# motor.net
KiCad netlist of a schematic drawn in Altium Designer
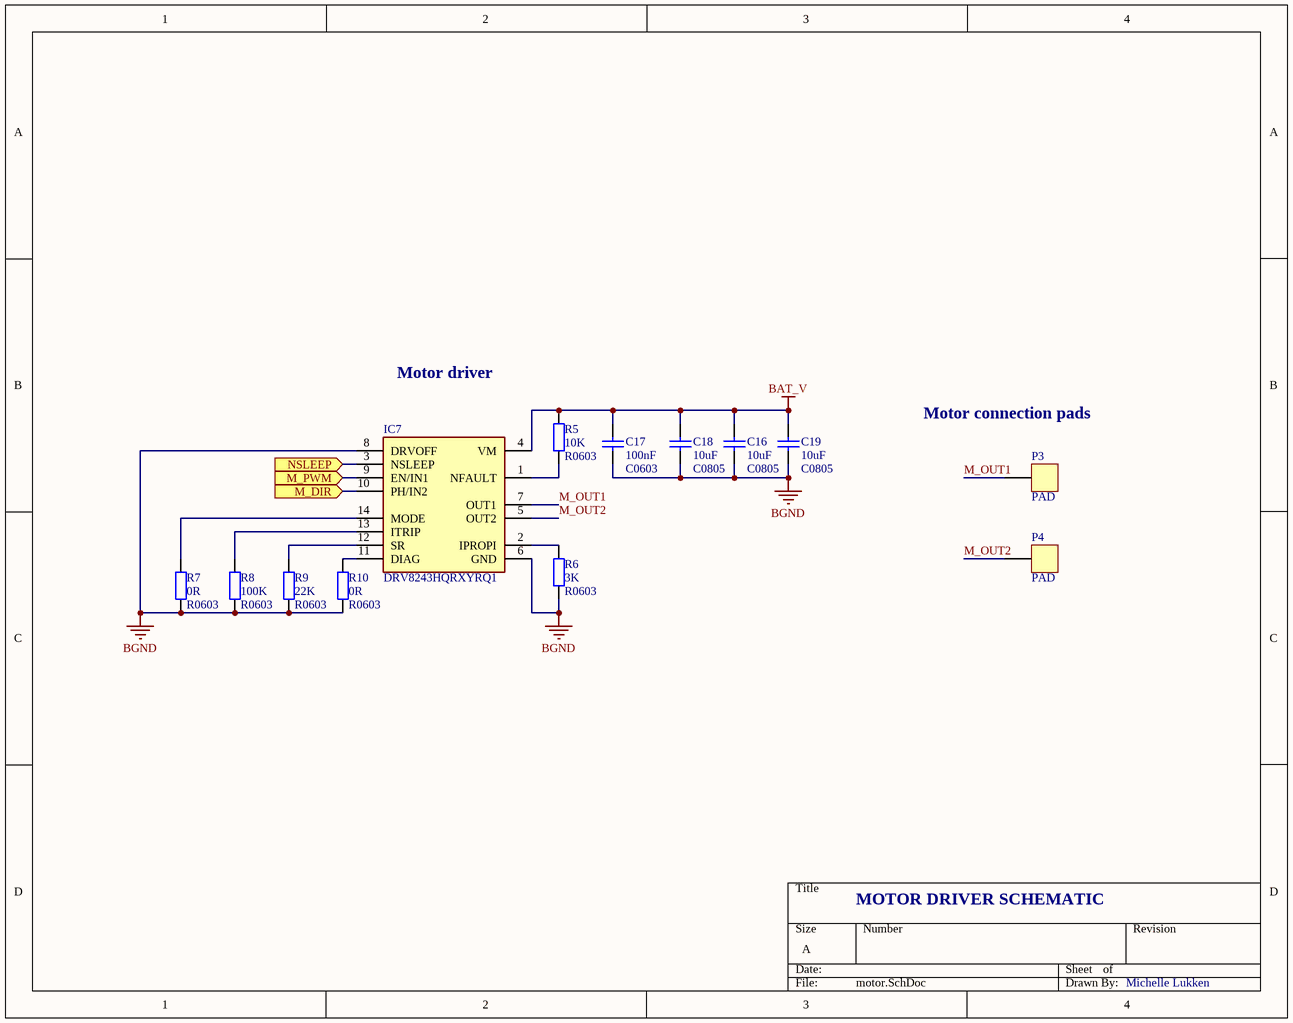
[diagram p0: motor.SchDoc]

(export (version "E")
  (design (tool "Eeschema 10.0.6"))
  (components
    (comp (ref "C16")
      (value "10uF*V")
      (footprint "C0805")
      (description "Ceramic capacitor")
      (fields (field (name "CAPACITANCE") "10uF"))
      (libsource (lib "Component Library INTLIB") (part "Capacitor"))
    )
    (comp (ref "C17")
      (value "100nF*V")
      (footprint "PCB Passives:C0603")
      (description "Ceramic capacitor")
      (fields (field (name "CAPACITANCE") "100nF"))
      (libsource (lib "DeltaX_basketball_mikro") (part "Capacitor"))
    )
    (comp (ref "C18")
      (value "10uF*V")
      (footprint "C0805")
      (description "Ceramic capacitor")
      (fields (field (name "CAPACITANCE") "10uF"))
      (libsource (lib "Component Library INTLIB") (part "Capacitor"))
    )
    (comp (ref "C19")
      (value "10uF*V")
      (footprint "C0805")
      (description "Ceramic capacitor")
      (fields (field (name "CAPACITANCE") "10uF"))
      (libsource (lib "Component Library INTLIB") (part "Capacitor"))
    )
    (comp (ref "IC7")
      (value "DRV8243HQRXYRQ1")
      (footprint "SamacSys:DRV8243HQRXYRQ1")
      (description "Integrated Circuit")
      (libsource (lib "DeltaX_basketball_mikro") (part "DRV8243HQRXYRQ1"))
    )
    (comp (ref "P3")
      (value "PAD")
      (footprint "SamacSys:PAD")
      (libsource (lib "DeltaX_basketball_mikro") (part "PAD"))
    )
    (comp (ref "P4")
      (value "PAD")
      (footprint "SamacSys:PAD")
      (libsource (lib "DeltaX_basketball_mikro") (part "PAD"))
    )
    (comp (ref "R5")
      (value "10K")
      (footprint "R0603")
      (description "Resistor")
      (fields (field (name "RESISTANCE") "10K"))
      (libsource (lib "Component Library INTLIB") (part "Resistor"))
    )
    (comp (ref "R6")
      (value "3K")
      (footprint "R0603")
      (description "Resistor")
      (fields (field (name "RESISTANCE") "3K"))
      (libsource (lib "Component Library INTLIB") (part "Resistor"))
    )
    (comp (ref "R7")
      (value "0R")
      (footprint "R0603")
      (description "Resistor")
      (fields (field (name "RESISTANCE") "0R"))
      (libsource (lib "Component Library INTLIB") (part "Resistor"))
    )
    (comp (ref "R8")
      (value "100K")
      (footprint "R0603")
      (description "Resistor")
      (fields (field (name "RESISTANCE") "100K"))
      (libsource (lib "Component Library INTLIB") (part "Resistor"))
    )
    (comp (ref "R9")
      (value "22K")
      (footprint "R0603")
      (description "Resistor")
      (fields (field (name "RESISTANCE") "22K"))
      (libsource (lib "Component Library INTLIB") (part "Resistor"))
    )
    (comp (ref "R10")
      (value "0R")
      (footprint "R0603")
      (description "Resistor")
      (fields (field (name "RESISTANCE") "0R"))
      (libsource (lib "Component Library INTLIB") (part "Resistor"))
    )
  )
  (nets
    (net (code "1") (name "/M_DIR") (class "Default")
      (node (ref "IC7") (pin "10") (pinfunction "PH/IN2_10") (pintype "passive"))
    )
    (net (code "2") (name "/M_OUT1") (class "Default")
      (node (ref "IC7") (pin "7") (pinfunction "OUT1_7") (pintype "passive"))
      (node (ref "P3") (pin "1") (pinfunction "PAD_1") (pintype "passive"))
    )
    (net (code "3") (name "/M_OUT2") (class "Default")
      (node (ref "IC7") (pin "5") (pinfunction "OUT2_5") (pintype "passive"))
      (node (ref "P4") (pin "1") (pinfunction "PAD_1") (pintype "passive"))
    )
    (net (code "4") (name "/M_PWM") (class "Default")
      (node (ref "IC7") (pin "9") (pinfunction "EN/IN1_9") (pintype "passive"))
    )
    (net (code "5") (name "/NSLEEP") (class "Default")
      (node (ref "IC7") (pin "3") (pinfunction "NSLEEP_3") (pintype "passive"))
    )
    (net (code "6") (name "BAT_V") (class "Default")
      (node (ref "C16") (pin "2") (pinfunction "2_2") (pintype "passive"))
      (node (ref "C17") (pin "2") (pinfunction "2_2") (pintype "passive"))
      (node (ref "C18") (pin "2") (pinfunction "2_2") (pintype "passive"))
      (node (ref "C19") (pin "2") (pinfunction "2_2") (pintype "passive"))
      (node (ref "IC7") (pin "4") (pinfunction "VM_4") (pintype "passive"))
      (node (ref "R5") (pin "2") (pinfunction "2_2") (pintype "passive"))
    )
    (net (code "7") (name "BGND") (class "Default")
      (node (ref "C16") (pin "1") (pinfunction "1_1") (pintype "passive"))
      (node (ref "C17") (pin "1") (pinfunction "1_1") (pintype "passive"))
      (node (ref "C18") (pin "1") (pinfunction "1_1") (pintype "passive"))
      (node (ref "C19") (pin "1") (pinfunction "1_1") (pintype "passive"))
      (node (ref "IC7") (pin "6") (pinfunction "GND_6") (pintype "passive"))
      (node (ref "IC7") (pin "8") (pinfunction "DRVOFF_8") (pintype "passive"))
      (node (ref "R10") (pin "1") (pinfunction "1_1") (pintype "passive"))
      (node (ref "R6") (pin "1") (pinfunction "1_1") (pintype "passive"))
      (node (ref "R7") (pin "1") (pinfunction "1_1") (pintype "passive"))
      (node (ref "R8") (pin "1") (pinfunction "1_1") (pintype "passive"))
      (node (ref "R9") (pin "1") (pinfunction "1_1") (pintype "passive"))
    )
    (net (code "8") (name "Net-(IC7-DIAG)") (class "Default")
      (node (ref "IC7") (pin "11") (pinfunction "DIAG_11") (pintype "passive"))
      (node (ref "R10") (pin "2") (pinfunction "2_2") (pintype "passive"))
    )
    (net (code "9") (name "Net-(IC7-IPROPI)") (class "Default")
      (node (ref "IC7") (pin "2") (pinfunction "IPROPI_2") (pintype "passive"))
      (node (ref "R6") (pin "2") (pinfunction "2_2") (pintype "passive"))
    )
    (net (code "10") (name "Net-(IC7-ITRIP)") (class "Default")
      (node (ref "IC7") (pin "13") (pinfunction "ITRIP_13") (pintype "passive"))
      (node (ref "R8") (pin "2") (pinfunction "2_2") (pintype "passive"))
    )
    (net (code "11") (name "Net-(IC7-MODE)") (class "Default")
      (node (ref "IC7") (pin "14") (pinfunction "MODE_14") (pintype "passive"))
      (node (ref "R7") (pin "2") (pinfunction "2_2") (pintype "passive"))
    )
    (net (code "12") (name "Net-(IC7-NFAULT)") (class "Default")
      (node (ref "IC7") (pin "1") (pinfunction "NFAULT_1") (pintype "passive"))
      (node (ref "R5") (pin "1") (pinfunction "1_1") (pintype "passive"))
    )
    (net (code "13") (name "Net-(IC7-SR)") (class "Default")
      (node (ref "IC7") (pin "12") (pinfunction "SR_12") (pintype "passive"))
      (node (ref "R9") (pin "2") (pinfunction "2_2") (pintype "passive"))
    )
  )
)
